# ESP32_main.net
KiCad netlist of a schematic drawn in Altium Designer
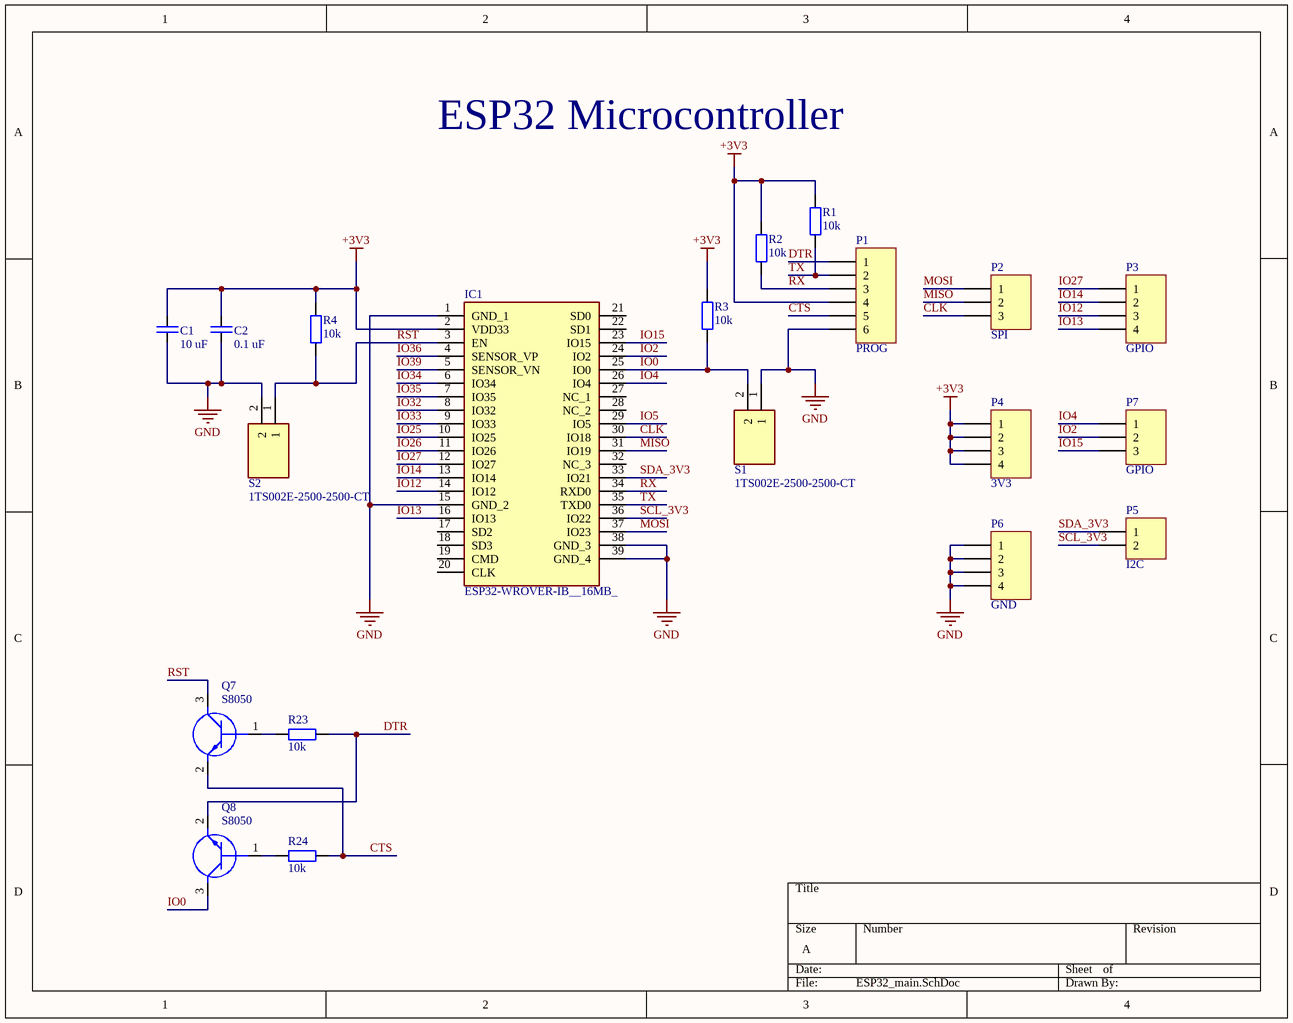
[diagram p0: ESP32_main.SchDoc]

(export (version "E")
  (design (tool "Eeschema 10.0.6"))
  (components
    (comp (ref "C1")
      (value "10 uF")
      (footprint "C2012_0805I_N")
      (description "Capacitor")
      (libsource (lib "General") (part "C"))
    )
    (comp (ref "C2")
      (value "0.1 uF")
      (footprint "C2012_0805I_N")
      (description "Capacitor")
      (libsource (lib "General") (part "C"))
    )
    (comp (ref "IC1")
      (value "ESP32-WROVER-IB__16MB_")
      (footprint "SamacSys:ESP32WROVERIB16MB")
      (description "Integrated Circuit")
      (fields
        (field (name "MANUFACTURER_PART_NUMBER") "ESP32-WROVER-IB (16MB)")
        (field (name "MOUSER PART NUMBER") "356-ESP32WROIB(16MB)")
      )
      (libsource (lib "SamacSys") (part "ESP32-WROVER-IB__16MB_"))
    )
    (comp (ref "P1")
      (value "PROG")
      (footprint "HDR1X6")
      (description "Header, 6-Pin")
      (fields (field (name "PUBLISHER") "Altium Limited"))
      (libsource (lib "Miscellaneous Connectors") (part "Header 6"))
    )
    (comp (ref "P2")
      (value "SPI")
      (footprint "HDR1X3")
      (description "Header, 3-Pin")
      (fields (field (name "PUBLISHER") "Altium Limited"))
      (libsource (lib "Miscellaneous Connectors") (part "Header 3"))
    )
    (comp (ref "P3")
      (value "GPIO")
      (footprint "HDR1X4")
      (description "Header, 4-Pin")
      (fields (field (name "PUBLISHER") "Altium Limited"))
      (libsource (lib "Miscellaneous Connectors") (part "Header 4"))
    )
    (comp (ref "P4")
      (value "3V3")
      (footprint "HDR1X4")
      (description "Header, 4-Pin")
      (fields (field (name "PUBLISHER") "Altium Limited"))
      (libsource (lib "Miscellaneous Connectors") (part "Header 4"))
    )
    (comp (ref "P5")
      (value "I2C")
      (footprint "HDR1X2")
      (description "Header, 2-Pin")
      (fields (field (name "PUBLISHER") "Altium Limited"))
      (libsource (lib "Miscellaneous Connectors") (part "Header 2"))
    )
    (comp (ref "P6")
      (value "GND")
      (footprint "HDR1X4")
      (description "Header, 4-Pin")
      (fields (field (name "PUBLISHER") "Altium Limited"))
      (libsource (lib "Miscellaneous Connectors") (part "Header 4"))
    )
    (comp (ref "P7")
      (value "GPIO")
      (footprint "HDR1X3")
      (description "Header, 3-Pin")
      (fields (field (name "PUBLISHER") "Altium Limited"))
      (libsource (lib "Miscellaneous Connectors") (part "Header 3"))
    )
    (comp (ref "Q7")
      (value "S8050")
      (footprint "SamacSys:SOT95P240X110-3N")
      (description "Transistor BJT NPN")
      (fields (field (name "MANUFACTURER_PART_NUMBER") "S8050G"))
      (libsource (lib "SamacSys") (part "S8050"))
    )
    (comp (ref "Q8")
      (value "S8050")
      (footprint "SamacSys:SOT95P240X110-3N")
      (description "Transistor BJT NPN")
      (fields (field (name "MANUFACTURER_PART_NUMBER") "S8050G"))
      (libsource (lib "SamacSys") (part "S8050"))
    )
    (comp (ref "R1")
      (value "10k")
      (footprint "R2012_0805I_N")
      (description "R")
      (libsource (lib "General") (part "R"))
    )
    (comp (ref "R2")
      (value "10k")
      (footprint "R2012_0805I_N")
      (description "R")
      (libsource (lib "General") (part "R"))
    )
    (comp (ref "R3")
      (value "10k")
      (footprint "R2012_0805I_N")
      (description "R")
      (libsource (lib "General") (part "R"))
    )
    (comp (ref "R4")
      (value "10k")
      (footprint "R2012_0805I_N")
      (description "R")
      (libsource (lib "General") (part "R"))
    )
    (comp (ref "R23")
      (value "10k")
      (footprint "R2012_0805I_N")
      (description "R")
      (libsource (lib "General") (part "R"))
    )
    (comp (ref "R24")
      (value "10k")
      (footprint "R2012_0805I_N")
      (description "R")
      (libsource (lib "General") (part "R"))
    )
    (comp (ref "S1")
      (value "1TS002E-2500-2500-CT")
      (footprint "1TS002E25002500CT")
      (description "Switch")
      (libsource (lib "SamacSys") (part "1TS002E-2500-2500-CT"))
    )
    (comp (ref "S2")
      (value "1TS002E-2500-2500-CT")
      (footprint "1TS002E25002500CT")
      (description "Switch")
      (libsource (lib "SamacSys") (part "1TS002E-2500-2500-CT"))
    )
  )
  (nets
    (net (code "1") (name "+3V3") (class "Default")
      (node (ref "C1") (pin "1") (pinfunction "1_1") (pintype "passive"))
      (node (ref "C2") (pin "1") (pinfunction "1_1") (pintype "passive"))
      (node (ref "IC1") (pin "2") (pinfunction "VDD33_2") (pintype "passive"))
      (node (ref "P1") (pin "4") (pinfunction "4_4") (pintype "passive"))
      (node (ref "P4") (pin "1") (pinfunction "1_1") (pintype "passive"))
      (node (ref "P4") (pin "2") (pinfunction "2_2") (pintype "passive"))
      (node (ref "P4") (pin "3") (pinfunction "3_3") (pintype "passive"))
      (node (ref "P4") (pin "4") (pinfunction "4_4") (pintype "passive"))
      (node (ref "R1") (pin "2") (pintype "passive"))
      (node (ref "R2") (pin "2") (pintype "passive"))
      (node (ref "R3") (pin "2") (pintype "passive"))
      (node (ref "R4") (pin "2") (pintype "passive"))
    )
    (net (code "2") (name "/CLK") (class "Default")
      (node (ref "IC1") (pin "30") (pinfunction "IO18_30") (pintype "passive"))
      (node (ref "P2") (pin "3") (pinfunction "3_3") (pintype "passive"))
    )
    (net (code "3") (name "/CTS") (class "Default")
      (node (ref "P1") (pin "5") (pinfunction "5_5") (pintype "passive"))
      (node (ref "Q7") (pin "2") (pinfunction "E_2") (pintype "passive"))
      (node (ref "R24") (pin "1") (pintype "passive"))
    )
    (net (code "4") (name "/DTR") (class "Default")
      (node (ref "P1") (pin "1") (pinfunction "1_1") (pintype "passive"))
      (node (ref "Q8") (pin "2") (pinfunction "E_2") (pintype "passive"))
      (node (ref "R23") (pin "1") (pintype "passive"))
    )
    (net (code "5") (name "/IO0") (class "Default")
      (node (ref "IC1") (pin "25") (pinfunction "IO0_25") (pintype "passive"))
      (node (ref "Q8") (pin "3") (pinfunction "C_3") (pintype "passive"))
      (node (ref "R3") (pin "1") (pintype "passive"))
      (node (ref "S1") (pin "2") (pinfunction "2_2") (pintype "passive"))
    )
    (net (code "6") (name "/IO2") (class "Default")
      (node (ref "IC1") (pin "24") (pinfunction "IO2_24") (pintype "passive"))
      (node (ref "P7") (pin "2") (pinfunction "2_2") (pintype "passive"))
    )
    (net (code "7") (name "/IO4") (class "Default")
      (node (ref "IC1") (pin "26") (pinfunction "IO4_26") (pintype "passive"))
      (node (ref "P7") (pin "1") (pinfunction "1_1") (pintype "passive"))
    )
    (net (code "8") (name "/IO5") (class "Default")
      (node (ref "IC1") (pin "29") (pinfunction "IO5_29") (pintype "passive"))
    )
    (net (code "9") (name "/IO12") (class "Default")
      (node (ref "IC1") (pin "14") (pinfunction "IO12_14") (pintype "passive"))
      (node (ref "P3") (pin "3") (pinfunction "3_3") (pintype "passive"))
    )
    (net (code "10") (name "/IO13") (class "Default")
      (node (ref "IC1") (pin "16") (pinfunction "IO13_16") (pintype "passive"))
      (node (ref "P3") (pin "4") (pinfunction "4_4") (pintype "passive"))
    )
    (net (code "11") (name "/IO14") (class "Default")
      (node (ref "IC1") (pin "13") (pinfunction "IO14_13") (pintype "passive"))
      (node (ref "P3") (pin "2") (pinfunction "2_2") (pintype "passive"))
    )
    (net (code "12") (name "/IO15") (class "Default")
      (node (ref "IC1") (pin "23") (pinfunction "IO15_23") (pintype "passive"))
      (node (ref "P7") (pin "3") (pinfunction "3_3") (pintype "passive"))
    )
    (net (code "13") (name "/IO25") (class "Default")
      (node (ref "IC1") (pin "10") (pinfunction "IO25_10") (pintype "passive"))
    )
    (net (code "14") (name "/IO26") (class "Default")
      (node (ref "IC1") (pin "11") (pinfunction "IO26_11") (pintype "passive"))
    )
    (net (code "15") (name "/IO27") (class "Default")
      (node (ref "IC1") (pin "12") (pinfunction "IO27_12") (pintype "passive"))
      (node (ref "P3") (pin "1") (pinfunction "1_1") (pintype "passive"))
    )
    (net (code "16") (name "/IO32") (class "Default")
      (node (ref "IC1") (pin "8") (pinfunction "IO32_8") (pintype "passive"))
    )
    (net (code "17") (name "/IO33") (class "Default")
      (node (ref "IC1") (pin "9") (pinfunction "IO33_9") (pintype "passive"))
    )
    (net (code "18") (name "/IO34") (class "Default")
      (node (ref "IC1") (pin "6") (pinfunction "IO34_6") (pintype "passive"))
    )
    (net (code "19") (name "/IO35") (class "Default")
      (node (ref "IC1") (pin "7") (pinfunction "IO35_7") (pintype "passive"))
    )
    (net (code "20") (name "/IO36") (class "Default")
      (node (ref "IC1") (pin "4") (pinfunction "SENSOR_VP_4") (pintype "passive"))
    )
    (net (code "21") (name "/IO39") (class "Default")
      (node (ref "IC1") (pin "5") (pinfunction "SENSOR_VN_5") (pintype "passive"))
    )
    (net (code "22") (name "/MISO") (class "Default")
      (node (ref "IC1") (pin "31") (pinfunction "IO19_31") (pintype "passive"))
      (node (ref "P2") (pin "2") (pinfunction "2_2") (pintype "passive"))
    )
    (net (code "23") (name "/MOSI") (class "Default")
      (node (ref "IC1") (pin "37") (pinfunction "IO23_37") (pintype "passive"))
      (node (ref "P2") (pin "1") (pinfunction "1_1") (pintype "passive"))
    )
    (net (code "24") (name "/RST") (class "Default")
      (node (ref "IC1") (pin "3") (pinfunction "EN_3") (pintype "passive"))
      (node (ref "Q7") (pin "3") (pinfunction "C_3") (pintype "passive"))
      (node (ref "R4") (pin "1") (pintype "passive"))
      (node (ref "S2") (pin "1") (pinfunction "1_1") (pintype "passive"))
    )
    (net (code "25") (name "/RX") (class "Default")
      (node (ref "IC1") (pin "34") (pinfunction "RXD0_34") (pintype "passive"))
      (node (ref "P1") (pin "3") (pinfunction "3_3") (pintype "passive"))
      (node (ref "R2") (pin "1") (pintype "passive"))
    )
    (net (code "26") (name "/SCL_3V3") (class "Default")
      (node (ref "IC1") (pin "36") (pinfunction "IO22_36") (pintype "passive"))
      (node (ref "P5") (pin "2") (pinfunction "2_2") (pintype "passive"))
    )
    (net (code "27") (name "/SDA_3V3") (class "Default")
      (node (ref "IC1") (pin "33") (pinfunction "IO21_33") (pintype "passive"))
      (node (ref "P5") (pin "1") (pinfunction "1_1") (pintype "passive"))
    )
    (net (code "28") (name "/TX") (class "Default")
      (node (ref "IC1") (pin "35") (pinfunction "TXD0_35") (pintype "passive"))
      (node (ref "P1") (pin "2") (pinfunction "2_2") (pintype "passive"))
      (node (ref "R1") (pin "1") (pintype "passive"))
    )
    (net (code "29") (name "GND") (class "Default")
      (node (ref "C1") (pin "2") (pinfunction "2_2") (pintype "passive"))
      (node (ref "C2") (pin "2") (pinfunction "2_2") (pintype "passive"))
      (node (ref "IC1") (pin "1") (pinfunction "GND_1_1") (pintype "passive"))
      (node (ref "IC1") (pin "15") (pinfunction "GND_2_15") (pintype "passive"))
      (node (ref "IC1") (pin "38") (pinfunction "GND_3_38") (pintype "passive"))
      (node (ref "IC1") (pin "39") (pinfunction "GND_4_39") (pintype "passive"))
      (node (ref "P1") (pin "6") (pinfunction "6_6") (pintype "passive"))
      (node (ref "P6") (pin "1") (pinfunction "1_1") (pintype "passive"))
      (node (ref "P6") (pin "2") (pinfunction "2_2") (pintype "passive"))
      (node (ref "P6") (pin "3") (pinfunction "3_3") (pintype "passive"))
      (node (ref "P6") (pin "4") (pinfunction "4_4") (pintype "passive"))
      (node (ref "S1") (pin "1") (pinfunction "1_1") (pintype "passive"))
      (node (ref "S2") (pin "2") (pinfunction "2_2") (pintype "passive"))
    )
    (net (code "30") (name "Net-(Q7-B)") (class "Default")
      (node (ref "Q7") (pin "1") (pinfunction "B_1") (pintype "passive"))
      (node (ref "R23") (pin "2") (pintype "passive"))
    )
    (net (code "31") (name "Net-(Q8-B)") (class "Default")
      (node (ref "Q8") (pin "1") (pinfunction "B_1") (pintype "passive"))
      (node (ref "R24") (pin "2") (pintype "passive"))
    )
    (net (code "32") (name "unconnected-(IC1-CLK-Pad20)") (class "Default")
      (node (ref "IC1") (pin "20") (pinfunction "CLK_20") (pintype "passive"))
    )
    (net (code "33") (name "unconnected-(IC1-CMD-Pad19)") (class "Default")
      (node (ref "IC1") (pin "19") (pinfunction "CMD_19") (pintype "passive"))
    )
    (net (code "34") (name "unconnected-(IC1-NC_1-Pad27)") (class "Default")
      (node (ref "IC1") (pin "27") (pinfunction "NC_1_27") (pintype "passive"))
    )
    (net (code "35") (name "unconnected-(IC1-NC_2-Pad28)") (class "Default")
      (node (ref "IC1") (pin "28") (pinfunction "NC_2_28") (pintype "passive"))
    )
    (net (code "36") (name "unconnected-(IC1-NC_3-Pad32)") (class "Default")
      (node (ref "IC1") (pin "32") (pinfunction "NC_3_32") (pintype "passive"))
    )
    (net (code "37") (name "unconnected-(IC1-SD0-Pad21)") (class "Default")
      (node (ref "IC1") (pin "21") (pinfunction "SD0_21") (pintype "passive"))
    )
    (net (code "38") (name "unconnected-(IC1-SD1-Pad22)") (class "Default")
      (node (ref "IC1") (pin "22") (pinfunction "SD1_22") (pintype "passive"))
    )
    (net (code "39") (name "unconnected-(IC1-SD2-Pad17)") (class "Default")
      (node (ref "IC1") (pin "17") (pinfunction "SD2_17") (pintype "passive"))
    )
    (net (code "40") (name "unconnected-(IC1-SD3-Pad18)") (class "Default")
      (node (ref "IC1") (pin "18") (pinfunction "SD3_18") (pintype "passive"))
    )
  )
)
